# positionsensing.net
KiCad netlist of a schematic drawn in Altium Designer
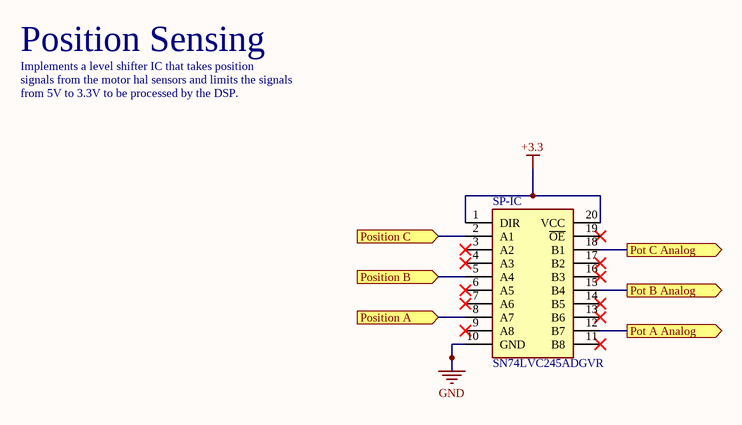
[diagram p0: positionsensing.SchDoc]

(export (version "E")
  (design (tool "Eeschema 10.0.6"))
  (components
    (comp (ref "SP-IC")
      (value "SN74LVC245ADGVR")
      (footprint "SamacSys:SOP40P640X120-20N")
      (description "Integrated Circuit")
      (fields (field (name "MOUSER PART NUMBER") "595-SN74LVC245ADGVR"))
      (libsource (lib "*") (part "SN74LVC245ADGVR"))
    )
  )
  (nets
    (net (code "1") (name "+3.3") (class "Default")
      (node (ref "SP-IC") (pin "1") (pinfunction "DIR_1") (pintype "passive"))
      (node (ref "SP-IC") (pin "20") (pinfunction "VCC_20") (pintype "passive"))
    )
    (net (code "2") (name "/Position A") (class "Default")
      (node (ref "SP-IC") (pin "8") (pinfunction "A7_8") (pintype "passive"))
    )
    (net (code "3") (name "/Position B") (class "Default")
      (node (ref "SP-IC") (pin "5") (pinfunction "A4_5") (pintype "passive"))
    )
    (net (code "4") (name "/Position C") (class "Default")
      (node (ref "SP-IC") (pin "2") (pinfunction "A1_2") (pintype "passive"))
    )
    (net (code "5") (name "/Pot A Analog") (class "Default")
      (node (ref "SP-IC") (pin "12") (pinfunction "B7_12") (pintype "passive"))
    )
    (net (code "6") (name "/Pot B Analog") (class "Default")
      (node (ref "SP-IC") (pin "15") (pinfunction "B4_15") (pintype "passive"))
    )
    (net (code "7") (name "/Pot C Analog") (class "Default")
      (node (ref "SP-IC") (pin "18") (pinfunction "B1_18") (pintype "passive"))
    )
    (net (code "8") (name "GND") (class "Default")
      (node (ref "SP-IC") (pin "10") (pinfunction "GND_10") (pintype "passive"))
    )
    (net (code "9") (name "unconnected-(SP-IC-A2-Pad3)") (class "Default")
      (node (ref "SP-IC") (pin "3") (pinfunction "A2_3") (pintype "passive+no_connect"))
    )
    (net (code "10") (name "unconnected-(SP-IC-A3-Pad4)") (class "Default")
      (node (ref "SP-IC") (pin "4") (pinfunction "A3_4") (pintype "passive+no_connect"))
    )
    (net (code "11") (name "unconnected-(SP-IC-A5-Pad6)") (class "Default")
      (node (ref "SP-IC") (pin "6") (pinfunction "A5_6") (pintype "passive+no_connect"))
    )
    (net (code "12") (name "unconnected-(SP-IC-A6-Pad7)") (class "Default")
      (node (ref "SP-IC") (pin "7") (pinfunction "A6_7") (pintype "passive+no_connect"))
    )
    (net (code "13") (name "unconnected-(SP-IC-A8-Pad9)") (class "Default")
      (node (ref "SP-IC") (pin "9") (pinfunction "A8_9") (pintype "passive+no_connect"))
    )
    (net (code "14") (name "unconnected-(SP-IC-B2-Pad17)") (class "Default")
      (node (ref "SP-IC") (pin "17") (pinfunction "B2_17") (pintype "passive+no_connect"))
    )
    (net (code "15") (name "unconnected-(SP-IC-B3-Pad16)") (class "Default")
      (node (ref "SP-IC") (pin "16") (pinfunction "B3_16") (pintype "passive+no_connect"))
    )
    (net (code "16") (name "unconnected-(SP-IC-B5-Pad14)") (class "Default")
      (node (ref "SP-IC") (pin "14") (pinfunction "B5_14") (pintype "passive+no_connect"))
    )
    (net (code "17") (name "unconnected-(SP-IC-B6-Pad13)") (class "Default")
      (node (ref "SP-IC") (pin "13") (pinfunction "B6_13") (pintype "passive+no_connect"))
    )
    (net (code "18") (name "unconnected-(SP-IC-B8-Pad11)") (class "Default")
      (node (ref "SP-IC") (pin "11") (pinfunction "B8_11") (pintype "passive+no_connect"))
    )
    (net (code "19") (name "unconnected-(SP-IC-~{OE}-Pad19)") (class "Default")
      (node (ref "SP-IC") (pin "19") (pinfunction "~{OE}_19") (pintype "passive+no_connect"))
    )
  )
)
